# SCH_lights_2024-05-02.net
KiCad netlist of a schematic drawn in EasyEDA
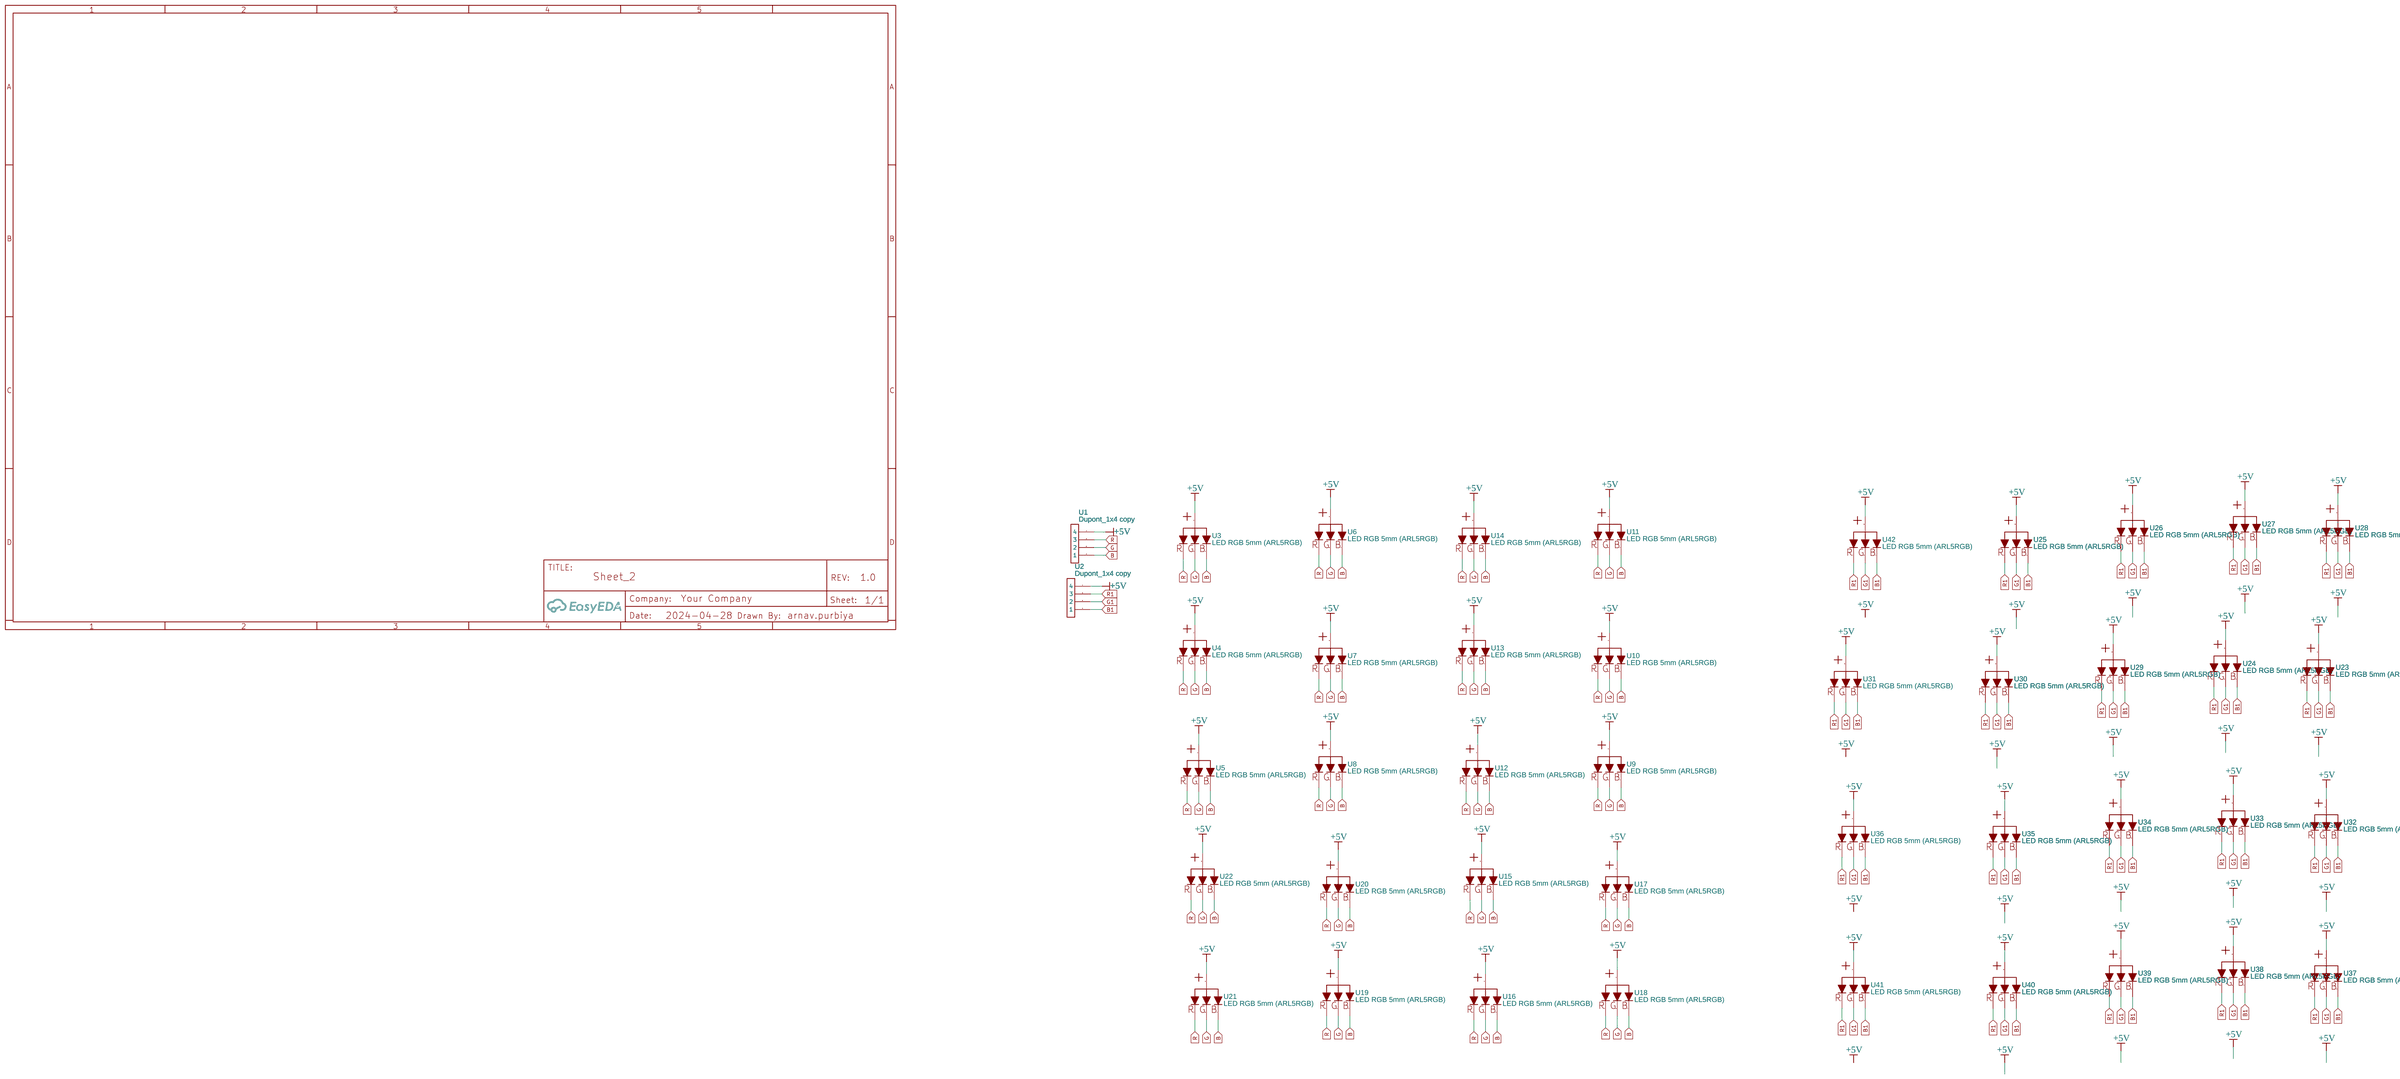
[diagram p0: schematic sheet]

(export (version "E")
  (design (tool "Eeschema 10.0.6"))
  (components
    (comp (ref "U1")
      (value "Dupont_1x4 copy")
      (fields (field (name "Manufacturer Part") "Conector_dupont"))
      (libsource (lib "") (part "Dupont_1x4 copy"))
    )
    (comp (ref "U2")
      (value "Dupont_1x4 copy")
      (fields (field (name "Manufacturer Part") "Conector_dupont"))
      (libsource (lib "") (part "Dupont_1x4 copy"))
    )
    (comp (ref "U3") (value "LED RGB 5mm (ARL5RGB)") (libsource (lib "") (part "LED RGB 5mm (ARL5RGB)")))
    (comp (ref "U4") (value "LED RGB 5mm (ARL5RGB)") (libsource (lib "") (part "LED RGB 5mm (ARL5RGB)")))
    (comp (ref "U5") (value "LED RGB 5mm (ARL5RGB)") (libsource (lib "") (part "LED RGB 5mm (ARL5RGB)")))
    (comp (ref "U6") (value "LED RGB 5mm (ARL5RGB)") (libsource (lib "") (part "LED RGB 5mm (ARL5RGB)")))
    (comp (ref "U7") (value "LED RGB 5mm (ARL5RGB)") (libsource (lib "") (part "LED RGB 5mm (ARL5RGB)")))
    (comp (ref "U8") (value "LED RGB 5mm (ARL5RGB)") (libsource (lib "") (part "LED RGB 5mm (ARL5RGB)")))
    (comp (ref "U9") (value "LED RGB 5mm (ARL5RGB)") (libsource (lib "") (part "LED RGB 5mm (ARL5RGB)")))
    (comp (ref "U10") (value "LED RGB 5mm (ARL5RGB)") (libsource (lib "") (part "LED RGB 5mm (ARL5RGB)")))
    (comp (ref "U11") (value "LED RGB 5mm (ARL5RGB)") (libsource (lib "") (part "LED RGB 5mm (ARL5RGB)")))
    (comp (ref "U12") (value "LED RGB 5mm (ARL5RGB)") (libsource (lib "") (part "LED RGB 5mm (ARL5RGB)")))
    (comp (ref "U13") (value "LED RGB 5mm (ARL5RGB)") (libsource (lib "") (part "LED RGB 5mm (ARL5RGB)")))
    (comp (ref "U14") (value "LED RGB 5mm (ARL5RGB)") (libsource (lib "") (part "LED RGB 5mm (ARL5RGB)")))
    (comp (ref "U15") (value "LED RGB 5mm (ARL5RGB)") (libsource (lib "") (part "LED RGB 5mm (ARL5RGB)")))
    (comp (ref "U16") (value "LED RGB 5mm (ARL5RGB)") (libsource (lib "") (part "LED RGB 5mm (ARL5RGB)")))
    (comp (ref "U17") (value "LED RGB 5mm (ARL5RGB)") (libsource (lib "") (part "LED RGB 5mm (ARL5RGB)")))
    (comp (ref "U18") (value "LED RGB 5mm (ARL5RGB)") (libsource (lib "") (part "LED RGB 5mm (ARL5RGB)")))
    (comp (ref "U19") (value "LED RGB 5mm (ARL5RGB)") (libsource (lib "") (part "LED RGB 5mm (ARL5RGB)")))
    (comp (ref "U20") (value "LED RGB 5mm (ARL5RGB)") (libsource (lib "") (part "LED RGB 5mm (ARL5RGB)")))
    (comp (ref "U21") (value "LED RGB 5mm (ARL5RGB)") (libsource (lib "") (part "LED RGB 5mm (ARL5RGB)")))
    (comp (ref "U22") (value "LED RGB 5mm (ARL5RGB)") (libsource (lib "") (part "LED RGB 5mm (ARL5RGB)")))
    (comp (ref "U23") (value "LED RGB 5mm (ARL5RGB)") (libsource (lib "") (part "LED RGB 5mm (ARL5RGB)")))
    (comp (ref "U24") (value "LED RGB 5mm (ARL5RGB)") (libsource (lib "") (part "LED RGB 5mm (ARL5RGB)")))
    (comp (ref "U25") (value "LED RGB 5mm (ARL5RGB)") (libsource (lib "") (part "LED RGB 5mm (ARL5RGB)")))
    (comp (ref "U26") (value "LED RGB 5mm (ARL5RGB)") (libsource (lib "") (part "LED RGB 5mm (ARL5RGB)")))
    (comp (ref "U27") (value "LED RGB 5mm (ARL5RGB)") (libsource (lib "") (part "LED RGB 5mm (ARL5RGB)")))
    (comp (ref "U28") (value "LED RGB 5mm (ARL5RGB)") (libsource (lib "") (part "LED RGB 5mm (ARL5RGB)")))
    (comp (ref "U29") (value "LED RGB 5mm (ARL5RGB)") (libsource (lib "") (part "LED RGB 5mm (ARL5RGB)")))
    (comp (ref "U30") (value "LED RGB 5mm (ARL5RGB)") (libsource (lib "") (part "LED RGB 5mm (ARL5RGB)")))
    (comp (ref "U31") (value "LED RGB 5mm (ARL5RGB)") (libsource (lib "") (part "LED RGB 5mm (ARL5RGB)")))
    (comp (ref "U32") (value "LED RGB 5mm (ARL5RGB)") (libsource (lib "") (part "LED RGB 5mm (ARL5RGB)")))
    (comp (ref "U33") (value "LED RGB 5mm (ARL5RGB)") (libsource (lib "") (part "LED RGB 5mm (ARL5RGB)")))
    (comp (ref "U34") (value "LED RGB 5mm (ARL5RGB)") (libsource (lib "") (part "LED RGB 5mm (ARL5RGB)")))
    (comp (ref "U35") (value "LED RGB 5mm (ARL5RGB)") (libsource (lib "") (part "LED RGB 5mm (ARL5RGB)")))
    (comp (ref "U36") (value "LED RGB 5mm (ARL5RGB)") (libsource (lib "") (part "LED RGB 5mm (ARL5RGB)")))
    (comp (ref "U37") (value "LED RGB 5mm (ARL5RGB)") (libsource (lib "") (part "LED RGB 5mm (ARL5RGB)")))
    (comp (ref "U38") (value "LED RGB 5mm (ARL5RGB)") (libsource (lib "") (part "LED RGB 5mm (ARL5RGB)")))
    (comp (ref "U39") (value "LED RGB 5mm (ARL5RGB)") (libsource (lib "") (part "LED RGB 5mm (ARL5RGB)")))
    (comp (ref "U40") (value "LED RGB 5mm (ARL5RGB)") (libsource (lib "") (part "LED RGB 5mm (ARL5RGB)")))
    (comp (ref "U41") (value "LED RGB 5mm (ARL5RGB)") (libsource (lib "") (part "LED RGB 5mm (ARL5RGB)")))
    (comp (ref "U42") (value "LED RGB 5mm (ARL5RGB)") (libsource (lib "") (part "LED RGB 5mm (ARL5RGB)")))
  )
  (nets
    (net (code "1") (name "+5V") (class "Default")
      (node (ref "U1") (pin "4") (pinfunction "4_4") (pintype "unspecified"))
      (node (ref "U10") (pin "2") (pinfunction "4_2") (pintype "unspecified"))
      (node (ref "U11") (pin "2") (pinfunction "4_2") (pintype "unspecified"))
      (node (ref "U12") (pin "2") (pinfunction "4_2") (pintype "unspecified"))
      (node (ref "U13") (pin "2") (pinfunction "4_2") (pintype "unspecified"))
      (node (ref "U14") (pin "2") (pinfunction "4_2") (pintype "unspecified"))
      (node (ref "U15") (pin "2") (pinfunction "4_2") (pintype "unspecified"))
      (node (ref "U16") (pin "2") (pinfunction "4_2") (pintype "unspecified"))
      (node (ref "U17") (pin "2") (pinfunction "4_2") (pintype "unspecified"))
      (node (ref "U18") (pin "2") (pinfunction "4_2") (pintype "unspecified"))
      (node (ref "U19") (pin "2") (pinfunction "4_2") (pintype "unspecified"))
      (node (ref "U2") (pin "4") (pinfunction "4_4") (pintype "unspecified"))
      (node (ref "U20") (pin "2") (pinfunction "4_2") (pintype "unspecified"))
      (node (ref "U21") (pin "2") (pinfunction "4_2") (pintype "unspecified"))
      (node (ref "U22") (pin "2") (pinfunction "4_2") (pintype "unspecified"))
      (node (ref "U23") (pin "2") (pinfunction "4_2") (pintype "unspecified"))
      (node (ref "U24") (pin "2") (pinfunction "4_2") (pintype "unspecified"))
      (node (ref "U25") (pin "2") (pinfunction "4_2") (pintype "unspecified"))
      (node (ref "U26") (pin "2") (pinfunction "4_2") (pintype "unspecified"))
      (node (ref "U27") (pin "2") (pinfunction "4_2") (pintype "unspecified"))
      (node (ref "U28") (pin "2") (pinfunction "4_2") (pintype "unspecified"))
      (node (ref "U29") (pin "2") (pinfunction "4_2") (pintype "unspecified"))
      (node (ref "U3") (pin "2") (pinfunction "4_2") (pintype "unspecified"))
      (node (ref "U30") (pin "2") (pinfunction "4_2") (pintype "unspecified"))
      (node (ref "U31") (pin "2") (pinfunction "4_2") (pintype "unspecified"))
      (node (ref "U32") (pin "2") (pinfunction "4_2") (pintype "unspecified"))
      (node (ref "U33") (pin "2") (pinfunction "4_2") (pintype "unspecified"))
      (node (ref "U34") (pin "2") (pinfunction "4_2") (pintype "unspecified"))
      (node (ref "U35") (pin "2") (pinfunction "4_2") (pintype "unspecified"))
      (node (ref "U36") (pin "2") (pinfunction "4_2") (pintype "unspecified"))
      (node (ref "U37") (pin "2") (pinfunction "4_2") (pintype "unspecified"))
      (node (ref "U38") (pin "2") (pinfunction "4_2") (pintype "unspecified"))
      (node (ref "U39") (pin "2") (pinfunction "4_2") (pintype "unspecified"))
      (node (ref "U4") (pin "2") (pinfunction "4_2") (pintype "unspecified"))
      (node (ref "U40") (pin "2") (pinfunction "4_2") (pintype "unspecified"))
      (node (ref "U41") (pin "2") (pinfunction "4_2") (pintype "unspecified"))
      (node (ref "U42") (pin "2") (pinfunction "4_2") (pintype "unspecified"))
      (node (ref "U5") (pin "2") (pinfunction "4_2") (pintype "unspecified"))
      (node (ref "U6") (pin "2") (pinfunction "4_2") (pintype "unspecified"))
      (node (ref "U7") (pin "2") (pinfunction "4_2") (pintype "unspecified"))
      (node (ref "U8") (pin "2") (pinfunction "4_2") (pintype "unspecified"))
      (node (ref "U9") (pin "2") (pinfunction "4_2") (pintype "unspecified"))
    )
    (net (code "2") (name "B") (class "Default")
      (node (ref "U1") (pin "1") (pinfunction "1_1") (pintype "unspecified"))
      (node (ref "U10") (pin "4") (pinfunction "3_4") (pintype "unspecified"))
      (node (ref "U11") (pin "4") (pinfunction "3_4") (pintype "unspecified"))
      (node (ref "U12") (pin "4") (pinfunction "3_4") (pintype "unspecified"))
      (node (ref "U13") (pin "4") (pinfunction "3_4") (pintype "unspecified"))
      (node (ref "U14") (pin "4") (pinfunction "3_4") (pintype "unspecified"))
      (node (ref "U15") (pin "4") (pinfunction "3_4") (pintype "unspecified"))
      (node (ref "U16") (pin "4") (pinfunction "3_4") (pintype "unspecified"))
      (node (ref "U17") (pin "4") (pinfunction "3_4") (pintype "unspecified"))
      (node (ref "U18") (pin "4") (pinfunction "3_4") (pintype "unspecified"))
      (node (ref "U19") (pin "4") (pinfunction "3_4") (pintype "unspecified"))
      (node (ref "U20") (pin "4") (pinfunction "3_4") (pintype "unspecified"))
      (node (ref "U21") (pin "4") (pinfunction "3_4") (pintype "unspecified"))
      (node (ref "U22") (pin "4") (pinfunction "3_4") (pintype "unspecified"))
      (node (ref "U3") (pin "4") (pinfunction "3_4") (pintype "unspecified"))
      (node (ref "U4") (pin "4") (pinfunction "3_4") (pintype "unspecified"))
      (node (ref "U5") (pin "4") (pinfunction "3_4") (pintype "unspecified"))
      (node (ref "U6") (pin "4") (pinfunction "3_4") (pintype "unspecified"))
      (node (ref "U7") (pin "4") (pinfunction "3_4") (pintype "unspecified"))
      (node (ref "U8") (pin "4") (pinfunction "3_4") (pintype "unspecified"))
      (node (ref "U9") (pin "4") (pinfunction "3_4") (pintype "unspecified"))
    )
    (net (code "3") (name "B1") (class "Default")
      (node (ref "U2") (pin "1") (pinfunction "1_1") (pintype "unspecified"))
      (node (ref "U23") (pin "4") (pinfunction "3_4") (pintype "unspecified"))
      (node (ref "U24") (pin "4") (pinfunction "3_4") (pintype "unspecified"))
      (node (ref "U25") (pin "4") (pinfunction "3_4") (pintype "unspecified"))
      (node (ref "U26") (pin "4") (pinfunction "3_4") (pintype "unspecified"))
      (node (ref "U27") (pin "4") (pinfunction "3_4") (pintype "unspecified"))
      (node (ref "U28") (pin "4") (pinfunction "3_4") (pintype "unspecified"))
      (node (ref "U29") (pin "4") (pinfunction "3_4") (pintype "unspecified"))
      (node (ref "U30") (pin "4") (pinfunction "3_4") (pintype "unspecified"))
      (node (ref "U31") (pin "4") (pinfunction "3_4") (pintype "unspecified"))
      (node (ref "U32") (pin "4") (pinfunction "3_4") (pintype "unspecified"))
      (node (ref "U33") (pin "4") (pinfunction "3_4") (pintype "unspecified"))
      (node (ref "U34") (pin "4") (pinfunction "3_4") (pintype "unspecified"))
      (node (ref "U35") (pin "4") (pinfunction "3_4") (pintype "unspecified"))
      (node (ref "U36") (pin "4") (pinfunction "3_4") (pintype "unspecified"))
      (node (ref "U37") (pin "4") (pinfunction "3_4") (pintype "unspecified"))
      (node (ref "U38") (pin "4") (pinfunction "3_4") (pintype "unspecified"))
      (node (ref "U39") (pin "4") (pinfunction "3_4") (pintype "unspecified"))
      (node (ref "U40") (pin "4") (pinfunction "3_4") (pintype "unspecified"))
      (node (ref "U41") (pin "4") (pinfunction "3_4") (pintype "unspecified"))
      (node (ref "U42") (pin "4") (pinfunction "3_4") (pintype "unspecified"))
    )
    (net (code "4") (name "G") (class "Default")
      (node (ref "U1") (pin "2") (pinfunction "2_2") (pintype "unspecified"))
      (node (ref "U10") (pin "3") (pinfunction "2_3") (pintype "unspecified"))
      (node (ref "U11") (pin "3") (pinfunction "2_3") (pintype "unspecified"))
      (node (ref "U12") (pin "3") (pinfunction "2_3") (pintype "unspecified"))
      (node (ref "U13") (pin "3") (pinfunction "2_3") (pintype "unspecified"))
      (node (ref "U14") (pin "3") (pinfunction "2_3") (pintype "unspecified"))
      (node (ref "U15") (pin "3") (pinfunction "2_3") (pintype "unspecified"))
      (node (ref "U16") (pin "3") (pinfunction "2_3") (pintype "unspecified"))
      (node (ref "U17") (pin "3") (pinfunction "2_3") (pintype "unspecified"))
      (node (ref "U18") (pin "3") (pinfunction "2_3") (pintype "unspecified"))
      (node (ref "U19") (pin "3") (pinfunction "2_3") (pintype "unspecified"))
      (node (ref "U20") (pin "3") (pinfunction "2_3") (pintype "unspecified"))
      (node (ref "U21") (pin "3") (pinfunction "2_3") (pintype "unspecified"))
      (node (ref "U22") (pin "3") (pinfunction "2_3") (pintype "unspecified"))
      (node (ref "U3") (pin "3") (pinfunction "2_3") (pintype "unspecified"))
      (node (ref "U4") (pin "3") (pinfunction "2_3") (pintype "unspecified"))
      (node (ref "U5") (pin "3") (pinfunction "2_3") (pintype "unspecified"))
      (node (ref "U6") (pin "3") (pinfunction "2_3") (pintype "unspecified"))
      (node (ref "U7") (pin "3") (pinfunction "2_3") (pintype "unspecified"))
      (node (ref "U8") (pin "3") (pinfunction "2_3") (pintype "unspecified"))
      (node (ref "U9") (pin "3") (pinfunction "2_3") (pintype "unspecified"))
    )
    (net (code "5") (name "G1") (class "Default")
      (node (ref "U2") (pin "2") (pinfunction "2_2") (pintype "unspecified"))
      (node (ref "U23") (pin "3") (pinfunction "2_3") (pintype "unspecified"))
      (node (ref "U24") (pin "3") (pinfunction "2_3") (pintype "unspecified"))
      (node (ref "U25") (pin "3") (pinfunction "2_3") (pintype "unspecified"))
      (node (ref "U26") (pin "3") (pinfunction "2_3") (pintype "unspecified"))
      (node (ref "U27") (pin "3") (pinfunction "2_3") (pintype "unspecified"))
      (node (ref "U28") (pin "3") (pinfunction "2_3") (pintype "unspecified"))
      (node (ref "U29") (pin "3") (pinfunction "2_3") (pintype "unspecified"))
      (node (ref "U30") (pin "3") (pinfunction "2_3") (pintype "unspecified"))
      (node (ref "U31") (pin "3") (pinfunction "2_3") (pintype "unspecified"))
      (node (ref "U32") (pin "3") (pinfunction "2_3") (pintype "unspecified"))
      (node (ref "U33") (pin "3") (pinfunction "2_3") (pintype "unspecified"))
      (node (ref "U34") (pin "3") (pinfunction "2_3") (pintype "unspecified"))
      (node (ref "U35") (pin "3") (pinfunction "2_3") (pintype "unspecified"))
      (node (ref "U36") (pin "3") (pinfunction "2_3") (pintype "unspecified"))
      (node (ref "U37") (pin "3") (pinfunction "2_3") (pintype "unspecified"))
      (node (ref "U38") (pin "3") (pinfunction "2_3") (pintype "unspecified"))
      (node (ref "U39") (pin "3") (pinfunction "2_3") (pintype "unspecified"))
      (node (ref "U40") (pin "3") (pinfunction "2_3") (pintype "unspecified"))
      (node (ref "U41") (pin "3") (pinfunction "2_3") (pintype "unspecified"))
      (node (ref "U42") (pin "3") (pinfunction "2_3") (pintype "unspecified"))
    )
    (net (code "6") (name "R") (class "Default")
      (node (ref "U1") (pin "3") (pinfunction "3_3") (pintype "unspecified"))
      (node (ref "U10") (pin "1") (pinfunction "1_1") (pintype "unspecified"))
      (node (ref "U11") (pin "1") (pinfunction "1_1") (pintype "unspecified"))
      (node (ref "U12") (pin "1") (pinfunction "1_1") (pintype "unspecified"))
      (node (ref "U13") (pin "1") (pinfunction "1_1") (pintype "unspecified"))
      (node (ref "U14") (pin "1") (pinfunction "1_1") (pintype "unspecified"))
      (node (ref "U15") (pin "1") (pinfunction "1_1") (pintype "unspecified"))
      (node (ref "U16") (pin "1") (pinfunction "1_1") (pintype "unspecified"))
      (node (ref "U17") (pin "1") (pinfunction "1_1") (pintype "unspecified"))
      (node (ref "U18") (pin "1") (pinfunction "1_1") (pintype "unspecified"))
      (node (ref "U19") (pin "1") (pinfunction "1_1") (pintype "unspecified"))
      (node (ref "U20") (pin "1") (pinfunction "1_1") (pintype "unspecified"))
      (node (ref "U21") (pin "1") (pinfunction "1_1") (pintype "unspecified"))
      (node (ref "U22") (pin "1") (pinfunction "1_1") (pintype "unspecified"))
      (node (ref "U3") (pin "1") (pinfunction "1_1") (pintype "unspecified"))
      (node (ref "U4") (pin "1") (pinfunction "1_1") (pintype "unspecified"))
      (node (ref "U5") (pin "1") (pinfunction "1_1") (pintype "unspecified"))
      (node (ref "U6") (pin "1") (pinfunction "1_1") (pintype "unspecified"))
      (node (ref "U7") (pin "1") (pinfunction "1_1") (pintype "unspecified"))
      (node (ref "U8") (pin "1") (pinfunction "1_1") (pintype "unspecified"))
      (node (ref "U9") (pin "1") (pinfunction "1_1") (pintype "unspecified"))
    )
    (net (code "7") (name "R1") (class "Default")
      (node (ref "U2") (pin "3") (pinfunction "3_3") (pintype "unspecified"))
      (node (ref "U23") (pin "1") (pinfunction "1_1") (pintype "unspecified"))
      (node (ref "U24") (pin "1") (pinfunction "1_1") (pintype "unspecified"))
      (node (ref "U25") (pin "1") (pinfunction "1_1") (pintype "unspecified"))
      (node (ref "U26") (pin "1") (pinfunction "1_1") (pintype "unspecified"))
      (node (ref "U27") (pin "1") (pinfunction "1_1") (pintype "unspecified"))
      (node (ref "U28") (pin "1") (pinfunction "1_1") (pintype "unspecified"))
      (node (ref "U29") (pin "1") (pinfunction "1_1") (pintype "unspecified"))
      (node (ref "U30") (pin "1") (pinfunction "1_1") (pintype "unspecified"))
      (node (ref "U31") (pin "1") (pinfunction "1_1") (pintype "unspecified"))
      (node (ref "U32") (pin "1") (pinfunction "1_1") (pintype "unspecified"))
      (node (ref "U33") (pin "1") (pinfunction "1_1") (pintype "unspecified"))
      (node (ref "U34") (pin "1") (pinfunction "1_1") (pintype "unspecified"))
      (node (ref "U35") (pin "1") (pinfunction "1_1") (pintype "unspecified"))
      (node (ref "U36") (pin "1") (pinfunction "1_1") (pintype "unspecified"))
      (node (ref "U37") (pin "1") (pinfunction "1_1") (pintype "unspecified"))
      (node (ref "U38") (pin "1") (pinfunction "1_1") (pintype "unspecified"))
      (node (ref "U39") (pin "1") (pinfunction "1_1") (pintype "unspecified"))
      (node (ref "U40") (pin "1") (pinfunction "1_1") (pintype "unspecified"))
      (node (ref "U41") (pin "1") (pinfunction "1_1") (pintype "unspecified"))
      (node (ref "U42") (pin "1") (pinfunction "1_1") (pintype "unspecified"))
    )
  )
)
